# AstroEQ.net
KiCad netlist of a schematic drawn in EAGLE
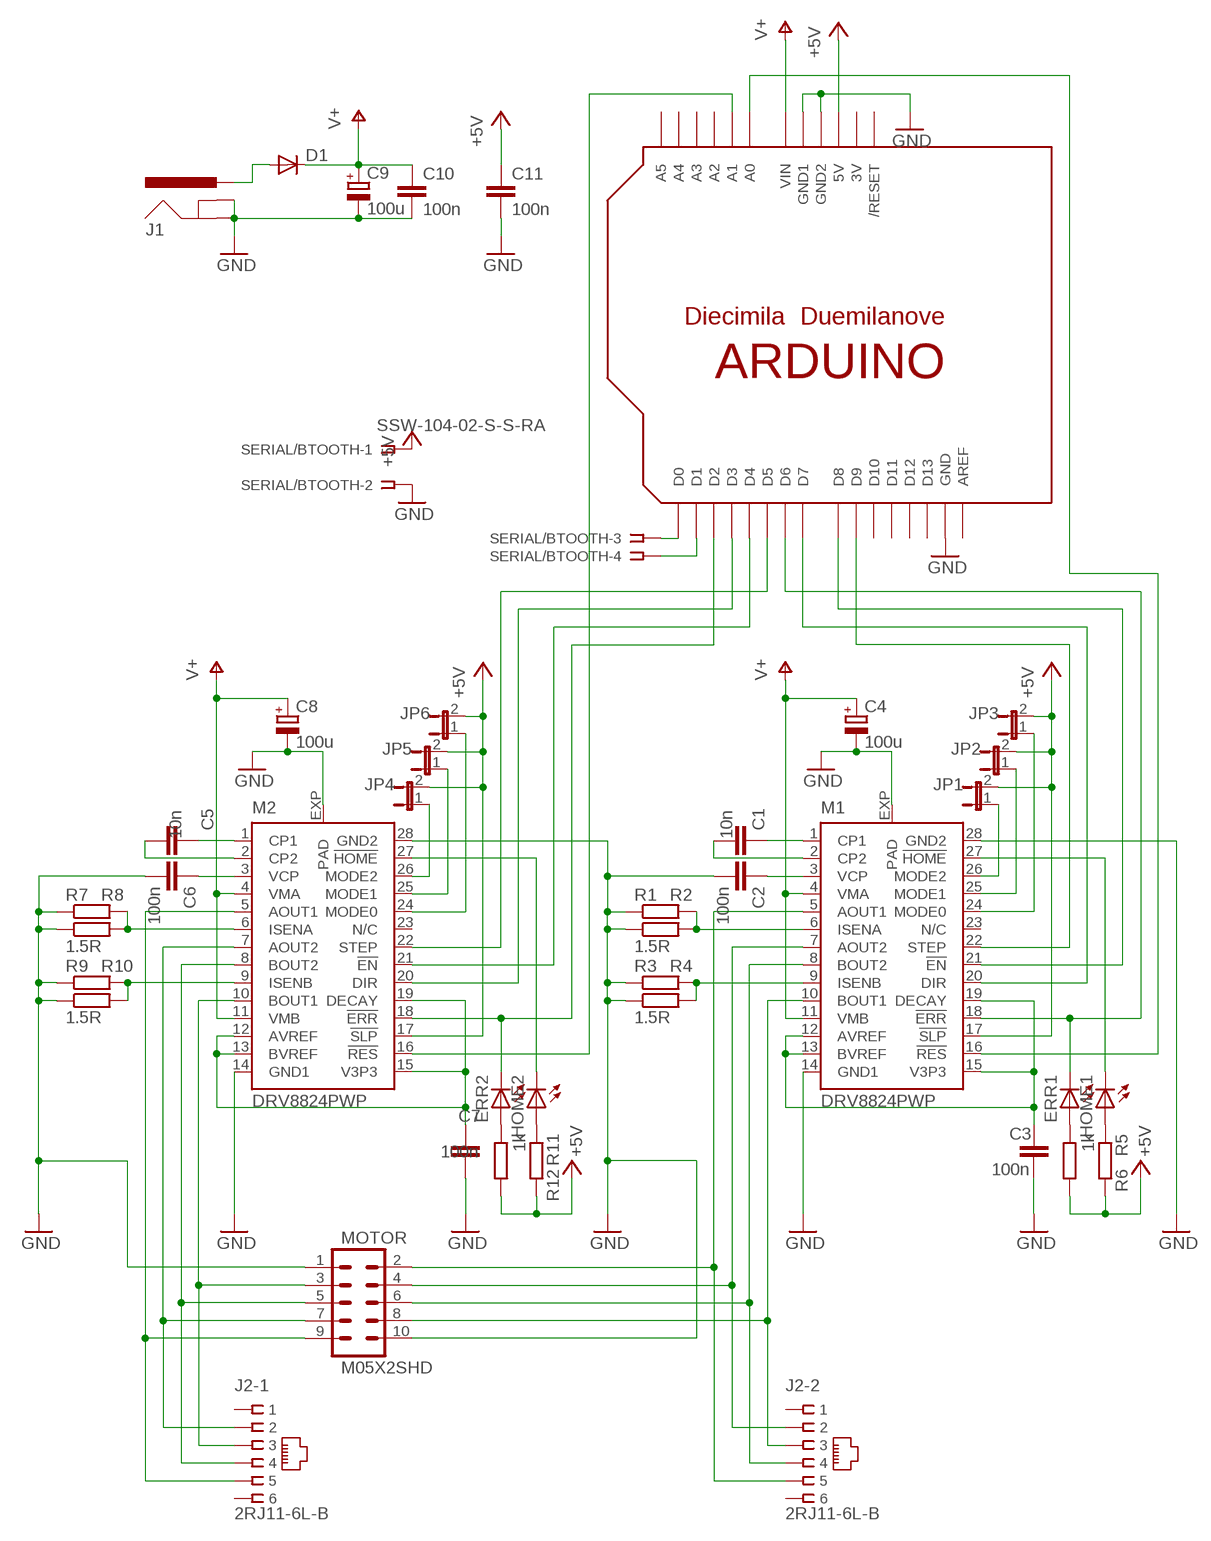
[diagram p0: schematic, sheet 1]

(export (version "E")
  (design (tool "Eeschema 10.0.6"))
  (components
    (comp (ref "C1")
      (value "10n")
      (footprint "eagle-import:C0603K")
      (libsource (lib "eagle-import") (part "C-EUC0603K"))
    )
    (comp (ref "C2")
      (value "100n")
      (footprint "eagle-import:C0603K")
      (libsource (lib "eagle-import") (part "C-EUC0603K"))
    )
    (comp (ref "C3")
      (value "100n")
      (footprint "eagle-import:C0603K")
      (libsource (lib "eagle-import") (part "C-EUC0603K"))
    )
    (comp (ref "C4")
      (value "100u")
      (footprint "eagle-import:C_6032-28R")
      (libsource (lib "eagle-import") (part "CPOL-EUC/6032-28R"))
    )
    (comp (ref "C5")
      (value "10n")
      (footprint "eagle-import:C0603K")
      (libsource (lib "eagle-import") (part "C-EUC0603K"))
    )
    (comp (ref "C6")
      (value "100n")
      (footprint "eagle-import:C0603K")
      (libsource (lib "eagle-import") (part "C-EUC0603K"))
    )
    (comp (ref "C7")
      (value "100n")
      (footprint "eagle-import:C0603K")
      (libsource (lib "eagle-import") (part "C-EUC0603K"))
    )
    (comp (ref "C8")
      (value "100u")
      (footprint "eagle-import:C_6032-28R")
      (libsource (lib "eagle-import") (part "CPOL-EUC/6032-28R"))
    )
    (comp (ref "C9")
      (value "100u")
      (footprint "eagle-import:C_6032-28R")
      (libsource (lib "eagle-import") (part "CPOL-EUC/6032-28R"))
    )
    (comp (ref "C10")
      (value "100n")
      (footprint "eagle-import:C0603K")
      (libsource (lib "eagle-import") (part "C-EUC0603K"))
    )
    (comp (ref "C11")
      (value "100n")
      (footprint "eagle-import:C0603K")
      (libsource (lib "eagle-import") (part "C-EUC0603K"))
    )
    (comp (ref "D1")
      (value "DIODESMA-ALT")
      (footprint "eagle-import:SMA-DIODE_ALT")
      (libsource (lib "eagle-import") (part "DIODESMA-ALT"))
    )
    (comp (ref "ERR1")
      (value "LEDCHIP-LED0603")
      (footprint "eagle-import:CHIP-LED0603")
      (libsource (lib "eagle-import") (part "LEDCHIP-LED0603"))
    )
    (comp (ref "ERR2")
      (value "LEDCHIP-LED0603")
      (footprint "eagle-import:CHIP-LED0603")
      (libsource (lib "eagle-import") (part "LEDCHIP-LED0603"))
    )
    (comp (ref "HOME1")
      (value "LEDCHIP-LED0603")
      (footprint "eagle-import:CHIP-LED0603")
      (libsource (lib "eagle-import") (part "LEDCHIP-LED0603"))
    )
    (comp (ref "HOME2")
      (value "LEDCHIP-LED0603")
      (footprint "eagle-import:CHIP-LED0603")
      (libsource (lib "eagle-import") (part "LEDCHIP-LED0603"))
    )
    (comp (ref "J1")
      (value "POWER_JACKPTH")
      (footprint "eagle-import:POWER_JACK_PTH")
      (libsource (lib "eagle-import") (part "POWER_JACKPTH"))
    )
    (comp (ref "J2")
      (value "2RJ11-6L-B")
      (footprint "eagle-import:2RJ11")
      (fields (field (name "MF") "TYCO ELECTRONICS"))
      (libsource (lib "eagle-import") (part "2RJ11-6L-B"))
    )
    (comp (ref "JP1")
      (value "JUMPER-2SMD-NO")
      (footprint "eagle-import:SJ_2S-NO")
      (libsource (lib "eagle-import") (part "JUMPER-2SMD-NO"))
    )
    (comp (ref "JP2")
      (value "JUMPER-2SMD-NO")
      (footprint "eagle-import:SJ_2S-NO")
      (libsource (lib "eagle-import") (part "JUMPER-2SMD-NO"))
    )
    (comp (ref "JP3")
      (value "JUMPER-2SMD-NO")
      (footprint "eagle-import:SJ_2S-NO")
      (libsource (lib "eagle-import") (part "JUMPER-2SMD-NO"))
    )
    (comp (ref "JP4")
      (value "JUMPER-2SMD-NO")
      (footprint "eagle-import:SJ_2S-NO")
      (libsource (lib "eagle-import") (part "JUMPER-2SMD-NO"))
    )
    (comp (ref "JP5")
      (value "JUMPER-2SMD-NO")
      (footprint "eagle-import:SJ_2S-NO")
      (libsource (lib "eagle-import") (part "JUMPER-2SMD-NO"))
    )
    (comp (ref "JP6")
      (value "JUMPER-2SMD-NO")
      (footprint "eagle-import:SJ_2S-NO")
      (libsource (lib "eagle-import") (part "JUMPER-2SMD-NO"))
    )
    (comp (ref "M1")
      (value "DRV8824PWP")
      (footprint "eagle-import:HTSSOP28PWP")
      (libsource (lib "eagle-import") (part "DRV8824PWP"))
    )
    (comp (ref "M2")
      (value "DRV8824PWP")
      (footprint "eagle-import:HTSSOP28PWP")
      (libsource (lib "eagle-import") (part "DRV8824PWP"))
    )
    (comp (ref "MOTOR")
      (value "M05X2SHD")
      (footprint "eagle-import:2X5-SHROUDED")
      (libsource (lib "eagle-import") (part "M05X2SHD"))
    )
    (comp (ref "R1")
      (value "1.5R")
      (footprint "eagle-import:R2512")
      (libsource (lib "eagle-import") (part "R-EU_R2512"))
    )
    (comp (ref "R2")
      (value "1.5R")
      (footprint "eagle-import:R2512")
      (libsource (lib "eagle-import") (part "R-EU_R2512"))
    )
    (comp (ref "R3")
      (value "1.5R")
      (footprint "eagle-import:R2512")
      (libsource (lib "eagle-import") (part "R-EU_R2512"))
    )
    (comp (ref "R4")
      (value "1.5R")
      (footprint "eagle-import:R2512")
      (libsource (lib "eagle-import") (part "R-EU_R2512"))
    )
    (comp (ref "R5")
      (value "1k")
      (footprint "eagle-import:R0603")
      (libsource (lib "eagle-import") (part "R-EU_R0603"))
    )
    (comp (ref "R6")
      (value "1k")
      (footprint "eagle-import:R0603")
      (libsource (lib "eagle-import") (part "R-EU_R0603"))
    )
    (comp (ref "R7")
      (value "1.5R")
      (footprint "eagle-import:R2512")
      (libsource (lib "eagle-import") (part "R-EU_R2512"))
    )
    (comp (ref "R8")
      (value "1.5R")
      (footprint "eagle-import:R2512")
      (libsource (lib "eagle-import") (part "R-EU_R2512"))
    )
    (comp (ref "R9")
      (value "1.5R")
      (footprint "eagle-import:R2512")
      (libsource (lib "eagle-import") (part "R-EU_R2512"))
    )
    (comp (ref "R10")
      (value "1.5R")
      (footprint "eagle-import:R2512")
      (libsource (lib "eagle-import") (part "R-EU_R2512"))
    )
    (comp (ref "R11")
      (value "1k")
      (footprint "eagle-import:R0603")
      (libsource (lib "eagle-import") (part "R-EU_R0603"))
    )
    (comp (ref "R12")
      (value "1k")
      (footprint "eagle-import:R0603")
      (libsource (lib "eagle-import") (part "R-EU_R0603"))
    )
    (comp (ref "SERIAL/BTOOTH")
      (value "SSW-104-02-S-S-RA")
      (footprint "eagle-import:SSW-104-02-S-S-RA")
      (libsource (lib "eagle-import") (part "SSW-104-02-S-S-RA"))
    )
    (comp (ref "U$1")
      (value "ARDUINOUNO")
      (footprint "eagle-import:ARDUINO")
      (libsource (lib "eagle-import") (part "ARDUINOUNO"))
    )
  )
  (nets
    (net (code "1") (name "+5V") (class "Default")
      (node (ref "C11") (pin "1") (pinfunction "1_1") (pintype "passive"))
      (node (ref "JP1") (pin "2") (pinfunction "2_2") (pintype "passive"))
      (node (ref "JP2") (pin "2") (pinfunction "2_2") (pintype "passive"))
      (node (ref "JP3") (pin "2") (pinfunction "2_2") (pintype "passive"))
      (node (ref "JP4") (pin "2") (pinfunction "2_2") (pintype "passive"))
      (node (ref "JP5") (pin "2") (pinfunction "2_2") (pintype "passive"))
      (node (ref "JP6") (pin "2") (pinfunction "2_2") (pintype "passive"))
      (node (ref "M1") (pin "17") (pinfunction "~{SLP}_17") (pintype "input"))
      (node (ref "M2") (pin "17") (pinfunction "~{SLP}_17") (pintype "input"))
      (node (ref "R11") (pin "2") (pinfunction "2_2") (pintype "passive"))
      (node (ref "R12") (pin "2") (pinfunction "2_2") (pintype "passive"))
      (node (ref "R5") (pin "2") (pinfunction "2_2") (pintype "passive"))
      (node (ref "R6") (pin "2") (pinfunction "2_2") (pintype "passive"))
      (node (ref "SERIAL/BTOOTH") (pin "1") (pinfunction "1_1") (pintype "passive"))
      (node (ref "U$1") (pin "5V") (pinfunction "5V_5V") (pintype "power_in"))
    )
    (net (code "2") (name "/3V") (class "Default")
      (node (ref "U$1") (pin "3V") (pinfunction "3V_3V") (pintype "power_in"))
    )
    (net (code "3") (name "GND") (class "Default")
      (node (ref "C10") (pin "2") (pinfunction "2_2") (pintype "passive"))
      (node (ref "C11") (pin "2") (pinfunction "2_2") (pintype "passive"))
      (node (ref "C2") (pin "2") (pinfunction "2_2") (pintype "passive"))
      (node (ref "C3") (pin "2") (pinfunction "2_2") (pintype "passive"))
      (node (ref "C4") (pin "-") (pinfunction "-_-") (pintype "passive"))
      (node (ref "C6") (pin "2") (pinfunction "2_2") (pintype "passive"))
      (node (ref "C7") (pin "2") (pinfunction "2_2") (pintype "passive"))
      (node (ref "C8") (pin "-") (pinfunction "-_-") (pintype "passive"))
      (node (ref "C9") (pin "-") (pinfunction "-_-") (pintype "passive"))
      (node (ref "J1") (pin "GND") (pinfunction "GND_GND") (pintype "bidirectional"))
      (node (ref "J1") (pin "GNDBREAK") (pinfunction "GNDBREAK_GNDBREAK") (pintype "bidirectional"))
      (node (ref "M1") (pin "14") (pinfunction "GND1_14") (pintype "power_in"))
      (node (ref "M1") (pin "28") (pinfunction "GND2_28") (pintype "power_in"))
      (node (ref "M1") (pin "EXP") (pinfunction "PAD_EXP") (pintype "power_in"))
      (node (ref "M2") (pin "14") (pinfunction "GND1_14") (pintype "power_in"))
      (node (ref "M2") (pin "28") (pinfunction "GND2_28") (pintype "power_in"))
      (node (ref "M2") (pin "EXP") (pinfunction "PAD_EXP") (pintype "power_in"))
      (node (ref "MOTOR") (pin "1") (pinfunction "1_1") (pintype "passive"))
      (node (ref "MOTOR") (pin "10") (pinfunction "10_10") (pintype "passive"))
      (node (ref "R1") (pin "1") (pinfunction "1_1") (pintype "passive"))
      (node (ref "R10") (pin "1") (pinfunction "1_1") (pintype "passive"))
      (node (ref "R2") (pin "1") (pinfunction "1_1") (pintype "passive"))
      (node (ref "R3") (pin "1") (pinfunction "1_1") (pintype "passive"))
      (node (ref "R4") (pin "1") (pinfunction "1_1") (pintype "passive"))
      (node (ref "R7") (pin "1") (pinfunction "1_1") (pintype "passive"))
      (node (ref "R8") (pin "1") (pinfunction "1_1") (pintype "passive"))
      (node (ref "R9") (pin "1") (pinfunction "1_1") (pintype "passive"))
      (node (ref "SERIAL/BTOOTH") (pin "2") (pinfunction "1_2") (pintype "passive"))
      (node (ref "U$1") (pin "GND") (pinfunction "GND_GND") (pintype "power_in"))
      (node (ref "U$1") (pin "GND1") (pinfunction "GND1_GND1") (pintype "power_in"))
      (node (ref "U$1") (pin "GND2") (pinfunction "GND2_GND2") (pintype "power_in"))
    )
    (net (code "4") (name "Net-(D1-PadA)") (class "Default")
      (node (ref "D1") (pin "A") (pinfunction "A_A") (pintype "passive"))
      (node (ref "J1") (pin "PWR") (pinfunction "PWR_PWR") (pintype "bidirectional"))
    )
    (net (code "5") (name "Net-(ERR1-PadA)") (class "Default")
      (node (ref "ERR1") (pin "A") (pinfunction "A_A") (pintype "passive"))
      (node (ref "R6") (pin "1") (pinfunction "1_1") (pintype "passive"))
    )
    (net (code "6") (name "Net-(ERR2-PadA)") (class "Default")
      (node (ref "ERR2") (pin "A") (pinfunction "A_A") (pintype "passive"))
      (node (ref "R12") (pin "1") (pinfunction "1_1") (pintype "passive"))
    )
    (net (code "7") (name "Net-(HOME1-PadA)") (class "Default")
      (node (ref "HOME1") (pin "A") (pinfunction "A_A") (pintype "passive"))
      (node (ref "R5") (pin "1") (pinfunction "1_1") (pintype "passive"))
    )
    (net (code "8") (name "Net-(HOME2-PadA)") (class "Default")
      (node (ref "HOME2") (pin "A") (pinfunction "A_A") (pintype "passive"))
      (node (ref "R11") (pin "1") (pinfunction "1_1") (pintype "passive"))
    )
    (net (code "9") (name "Net-(J2A-2)") (class "Default")
      (node (ref "J2") (pin "1-2") (pinfunction "2_1-2") (pintype "passive"))
      (node (ref "M2") (pin "7") (pinfunction "AOUT2_7") (pintype "output"))
      (node (ref "MOTOR") (pin "7") (pinfunction "7_7") (pintype "passive"))
    )
    (net (code "10") (name "Net-(J2A-3)") (class "Default")
      (node (ref "J2") (pin "1-3") (pinfunction "3_1-3") (pintype "passive"))
      (node (ref "M2") (pin "10") (pinfunction "BOUT1_10") (pintype "output"))
      (node (ref "MOTOR") (pin "3") (pinfunction "3_3") (pintype "passive"))
    )
    (net (code "11") (name "Net-(J2A-4)") (class "Default")
      (node (ref "J2") (pin "1-4") (pinfunction "4_1-4") (pintype "passive"))
      (node (ref "M2") (pin "8") (pinfunction "BOUT2_8") (pintype "output"))
      (node (ref "MOTOR") (pin "5") (pinfunction "5_5") (pintype "passive"))
    )
    (net (code "12") (name "Net-(J2A-5)") (class "Default")
      (node (ref "J2") (pin "1-5") (pinfunction "5_1-5") (pintype "passive"))
      (node (ref "M2") (pin "5") (pinfunction "AOUT1_5") (pintype "output"))
      (node (ref "MOTOR") (pin "9") (pinfunction "9_9") (pintype "passive"))
    )
    (net (code "13") (name "Net-(J2B-2)") (class "Default")
      (node (ref "J2") (pin "2-2") (pinfunction "2_2-2") (pintype "passive"))
      (node (ref "M1") (pin "7") (pinfunction "AOUT2_7") (pintype "output"))
      (node (ref "MOTOR") (pin "4") (pinfunction "4_4") (pintype "passive"))
    )
    (net (code "14") (name "Net-(J2B-3)") (class "Default")
      (node (ref "J2") (pin "2-3") (pinfunction "3_2-3") (pintype "passive"))
      (node (ref "M1") (pin "10") (pinfunction "BOUT1_10") (pintype "output"))
      (node (ref "MOTOR") (pin "8") (pinfunction "8_8") (pintype "passive"))
    )
    (net (code "15") (name "Net-(J2B-4)") (class "Default")
      (node (ref "J2") (pin "2-4") (pinfunction "4_2-4") (pintype "passive"))
      (node (ref "M1") (pin "8") (pinfunction "BOUT2_8") (pintype "output"))
      (node (ref "MOTOR") (pin "6") (pinfunction "6_6") (pintype "passive"))
    )
    (net (code "16") (name "Net-(J2B-5)") (class "Default")
      (node (ref "J2") (pin "2-5") (pinfunction "5_2-5") (pintype "passive"))
      (node (ref "M1") (pin "5") (pinfunction "AOUT1_5") (pintype "output"))
      (node (ref "MOTOR") (pin "2") (pinfunction "2_2") (pintype "passive"))
    )
    (net (code "17") (name "Net-(M1-AVREF)") (class "Default")
      (node (ref "C3") (pin "1") (pinfunction "1_1") (pintype "passive"))
      (node (ref "M1") (pin "12") (pinfunction "AVREF_12") (pintype "input"))
      (node (ref "M1") (pin "13") (pinfunction "BVREF_13") (pintype "input"))
      (node (ref "M1") (pin "15") (pinfunction "V3P3_15") (pintype "output"))
      (node (ref "M1") (pin "19") (pinfunction "DECAY_19") (pintype "input"))
    )
    (net (code "18") (name "Net-(M1-CP1)") (class "Default")
      (node (ref "C1") (pin "1") (pinfunction "1_1") (pintype "passive"))
      (node (ref "M1") (pin "1") (pinfunction "CP1_1") (pintype "passive"))
    )
    (net (code "19") (name "Net-(M1-CP2)") (class "Default")
      (node (ref "C1") (pin "2") (pinfunction "2_2") (pintype "passive"))
      (node (ref "M1") (pin "2") (pinfunction "CP2_2") (pintype "passive"))
    )
    (net (code "20") (name "Net-(M1-DIR)") (class "Default")
      (node (ref "M1") (pin "20") (pinfunction "DIR_20") (pintype "input"))
      (node (ref "U$1") (pin "D7") (pinfunction "D7_D7") (pintype "bidirectional"))
    )
    (net (code "21") (name "Net-(M1-ISENA)") (class "Default")
      (node (ref "M1") (pin "6") (pinfunction "ISENA_6") (pintype "bidirectional"))
      (node (ref "R1") (pin "2") (pinfunction "2_2") (pintype "passive"))
      (node (ref "R2") (pin "2") (pinfunction "2_2") (pintype "passive"))
    )
    (net (code "22") (name "Net-(M1-ISENB)") (class "Default")
      (node (ref "M1") (pin "9") (pinfunction "ISENB_9") (pintype "bidirectional"))
      (node (ref "R3") (pin "2") (pinfunction "2_2") (pintype "passive"))
      (node (ref "R4") (pin "2") (pinfunction "2_2") (pintype "passive"))
    )
    (net (code "23") (name "Net-(M1-MODE0)") (class "Default")
      (node (ref "JP3") (pin "1") (pinfunction "1_1") (pintype "passive"))
      (node (ref "M1") (pin "24") (pinfunction "MODE0_24") (pintype "input"))
    )
    (net (code "24") (name "Net-(M1-MODE1)") (class "Default")
      (node (ref "JP2") (pin "1") (pinfunction "1_1") (pintype "passive"))
      (node (ref "M1") (pin "25") (pinfunction "MODE1_25") (pintype "input"))
    )
    (net (code "25") (name "Net-(M1-MODE2)") (class "Default")
      (node (ref "JP1") (pin "1") (pinfunction "1_1") (pintype "passive"))
      (node (ref "M1") (pin "26") (pinfunction "MODE2_26") (pintype "input"))
    )
    (net (code "26") (name "Net-(M1-STEP)") (class "Default")
      (node (ref "M1") (pin "22") (pinfunction "STEP_22") (pintype "input"))
      (node (ref "U$1") (pin "D9") (pinfunction "D9_D9") (pintype "bidirectional"))
    )
    (net (code "27") (name "Net-(M1-VCP)") (class "Default")
      (node (ref "C2") (pin "1") (pinfunction "1_1") (pintype "passive"))
      (node (ref "M1") (pin "3") (pinfunction "VCP_3") (pintype "power_in"))
    )
    (net (code "28") (name "Net-(M1-~{EN})") (class "Default")
      (node (ref "M1") (pin "21") (pinfunction "~{EN}_21") (pintype "input"))
      (node (ref "U$1") (pin "D8") (pinfunction "D8_D8") (pintype "bidirectional"))
    )
    (net (code "29") (name "Net-(M1-~{ERR})") (class "Default")
      (node (ref "ERR1") (pin "C") (pinfunction "C_C") (pintype "passive"))
      (node (ref "M1") (pin "18") (pinfunction "~{ERR}_18") (pintype "output"))
      (node (ref "U$1") (pin "D6") (pinfunction "D6_D6") (pintype "bidirectional"))
    )
    (net (code "30") (name "Net-(M1-~{HOME})") (class "Default")
      (node (ref "HOME1") (pin "C") (pinfunction "C_C") (pintype "passive"))
      (node (ref "M1") (pin "27") (pinfunction "~{HOME}_27") (pintype "output"))
    )
    (net (code "31") (name "Net-(M1-~{RES})") (class "Default")
      (node (ref "M1") (pin "16") (pinfunction "~{RES}_16") (pintype "input"))
      (node (ref "U$1") (pin "A0") (pinfunction "A0_A0") (pintype "bidirectional"))
    )
    (net (code "32") (name "Net-(M2-AVREF)") (class "Default")
      (node (ref "C7") (pin "1") (pinfunction "1_1") (pintype "passive"))
      (node (ref "M2") (pin "12") (pinfunction "AVREF_12") (pintype "input"))
      (node (ref "M2") (pin "13") (pinfunction "BVREF_13") (pintype "input"))
      (node (ref "M2") (pin "15") (pinfunction "V3P3_15") (pintype "output"))
      (node (ref "M2") (pin "19") (pinfunction "DECAY_19") (pintype "input"))
    )
    (net (code "33") (name "Net-(M2-CP1)") (class "Default")
      (node (ref "C5") (pin "1") (pinfunction "1_1") (pintype "passive"))
      (node (ref "M2") (pin "1") (pinfunction "CP1_1") (pintype "passive"))
    )
    (net (code "34") (name "Net-(M2-CP2)") (class "Default")
      (node (ref "C5") (pin "2") (pinfunction "2_2") (pintype "passive"))
      (node (ref "M2") (pin "2") (pinfunction "CP2_2") (pintype "passive"))
    )
    (net (code "35") (name "Net-(M2-DIR)") (class "Default")
      (node (ref "M2") (pin "20") (pinfunction "DIR_20") (pintype "input"))
      (node (ref "U$1") (pin "D3") (pinfunction "D3_D3") (pintype "bidirectional"))
    )
    (net (code "36") (name "Net-(M2-ISENA)") (class "Default")
      (node (ref "M2") (pin "6") (pinfunction "ISENA_6") (pintype "bidirectional"))
      (node (ref "R7") (pin "2") (pinfunction "2_2") (pintype "passive"))
      (node (ref "R8") (pin "2") (pinfunction "2_2") (pintype "passive"))
    )
    (net (code "37") (name "Net-(M2-ISENB)") (class "Default")
      (node (ref "M2") (pin "9") (pinfunction "ISENB_9") (pintype "bidirectional"))
      (node (ref "R10") (pin "2") (pinfunction "2_2") (pintype "passive"))
      (node (ref "R9") (pin "2") (pinfunction "2_2") (pintype "passive"))
    )
    (net (code "38") (name "Net-(M2-MODE0)") (class "Default")
      (node (ref "JP6") (pin "1") (pinfunction "1_1") (pintype "passive"))
      (node (ref "M2") (pin "24") (pinfunction "MODE0_24") (pintype "input"))
    )
    (net (code "39") (name "Net-(M2-MODE1)") (class "Default")
      (node (ref "JP5") (pin "1") (pinfunction "1_1") (pintype "passive"))
      (node (ref "M2") (pin "25") (pinfunction "MODE1_25") (pintype "input"))
    )
    (net (code "40") (name "Net-(M2-MODE2)") (class "Default")
      (node (ref "JP4") (pin "1") (pinfunction "1_1") (pintype "passive"))
      (node (ref "M2") (pin "26") (pinfunction "MODE2_26") (pintype "input"))
    )
    (net (code "41") (name "Net-(M2-STEP)") (class "Default")
      (node (ref "M2") (pin "22") (pinfunction "STEP_22") (pintype "input"))
      (node (ref "U$1") (pin "D5") (pinfunction "D5_D5") (pintype "bidirectional"))
    )
    (net (code "42") (name "Net-(M2-VCP)") (class "Default")
      (node (ref "C6") (pin "1") (pinfunction "1_1") (pintype "passive"))
      (node (ref "M2") (pin "3") (pinfunction "VCP_3") (pintype "power_in"))
    )
    (net (code "43") (name "Net-(M2-~{EN})") (class "Default")
      (node (ref "M2") (pin "21") (pinfunction "~{EN}_21") (pintype "input"))
      (node (ref "U$1") (pin "D4") (pinfunction "D4_D4") (pintype "bidirectional"))
    )
    (net (code "44") (name "Net-(M2-~{ERR})") (class "Default")
      (node (ref "ERR2") (pin "C") (pinfunction "C_C") (pintype "passive"))
      (node (ref "M2") (pin "18") (pinfunction "~{ERR}_18") (pintype "output"))
      (node (ref "U$1") (pin "D2") (pinfunction "D2_D2") (pintype "bidirectional"))
    )
    (net (code "45") (name "Net-(M2-~{HOME})") (class "Default")
      (node (ref "HOME2") (pin "C") (pinfunction "C_C") (pintype "passive"))
      (node (ref "M2") (pin "27") (pinfunction "~{HOME}_27") (pintype "output"))
    )
    (net (code "46") (name "Net-(M2-~{RES})") (class "Default")
      (node (ref "M2") (pin "16") (pinfunction "~{RES}_16") (pintype "input"))
      (node (ref "U$1") (pin "A1") (pinfunction "A1_A1") (pintype "bidirectional"))
    )
    (net (code "47") (name "Net-(SERIAL/BTOOTHC-1)") (class "Default")
      (node (ref "SERIAL/BTOOTH") (pin "3") (pinfunction "1_3") (pintype "passive"))
      (node (ref "U$1") (pin "D0") (pinfunction "D0_D0") (pintype "bidirectional"))
    )
    (net (code "48") (name "Net-(SERIAL/BTOOTHD-1)") (class "Default")
      (node (ref "SERIAL/BTOOTH") (pin "4") (pinfunction "1_4") (pintype "passive"))
      (node (ref "U$1") (pin "D1") (pinfunction "D1_D1") (pintype "bidirectional"))
    )
    (net (code "49") (name "V+") (class "Default")
      (node (ref "C10") (pin "1") (pinfunction "1_1") (pintype "passive"))
      (node (ref "C4") (pin "+") (pinfunction "+_+") (pintype "passive"))
      (node (ref "C8") (pin "+") (pinfunction "+_+") (pintype "passive"))
      (node (ref "C9") (pin "+") (pinfunction "+_+") (pintype "passive"))
      (node (ref "D1") (pin "C") (pinfunction "C_C") (pintype "passive"))
      (node (ref "M1") (pin "11") (pinfunction "VMB_11") (pintype "power_in"))
      (node (ref "M1") (pin "4") (pinfunction "VMA_4") (pintype "power_in"))
      (node (ref "M2") (pin "11") (pinfunction "VMB_11") (pintype "power_in"))
      (node (ref "M2") (pin "4") (pinfunction "VMA_4") (pintype "power_in"))
      (node (ref "U$1") (pin "VIN") (pinfunction "VIN_VIN") (pintype "power_in"))
    )
    (net (code "50") (name "unconnected-(J2A-1-Pad1-1)") (class "Default")
      (node (ref "J2") (pin "1-1") (pinfunction "1_1-1") (pintype "passive"))
    )
    (net (code "51") (name "unconnected-(J2A-6-Pad1-6)") (class "Default")
      (node (ref "J2") (pin "1-6") (pinfunction "6_1-6") (pintype "passive"))
    )
    (net (code "52") (name "unconnected-(J2B-1-Pad2-1)") (class "Default")
      (node (ref "J2") (pin "2-1") (pinfunction "1_2-1") (pintype "passive"))
    )
    (net (code "53") (name "unconnected-(J2B-6-Pad2-6)") (class "Default")
      (node (ref "J2") (pin "2-6") (pinfunction "6_2-6") (pintype "passive"))
    )
    (net (code "54") (name "unconnected-(M1-N{slash}C-Pad23)") (class "Default")
      (node (ref "M1") (pin "23") (pinfunction "N/C_23") (pintype "no_connect"))
    )
    (net (code "55") (name "unconnected-(M2-N{slash}C-Pad23)") (class "Default")
      (node (ref "M2") (pin "23") (pinfunction "N/C_23") (pintype "no_connect"))
    )
    (net (code "56") (name "unconnected-(U$1-PadA2)") (class "Default")
      (node (ref "U$1") (pin "A2") (pinfunction "A2_A2") (pintype "bidirectional"))
    )
    (net (code "57") (name "unconnected-(U$1-PadA3)") (class "Default")
      (node (ref "U$1") (pin "A3") (pinfunction "A3_A3") (pintype "bidirectional"))
    )
    (net (code "58") (name "unconnected-(U$1-PadA4)") (class "Default")
      (node (ref "U$1") (pin "A4") (pinfunction "A4_A4") (pintype "bidirectional"))
    )
    (net (code "59") (name "unconnected-(U$1-PadA5)") (class "Default")
      (node (ref "U$1") (pin "A5") (pinfunction "A5_A5") (pintype "bidirectional"))
    )
    (net (code "60") (name "unconnected-(U$1-PadAREF)") (class "Default")
      (node (ref "U$1") (pin "AREF") (pinfunction "AREF_AREF") (pintype "bidirectional"))
    )
    (net (code "61") (name "unconnected-(U$1-PadD10)") (class "Default")
      (node (ref "U$1") (pin "D10") (pinfunction "D10_D10") (pintype "bidirectional"))
    )
    (net (code "62") (name "unconnected-(U$1-PadD11)") (class "Default")
      (node (ref "U$1") (pin "D11") (pinfunction "D11_D11") (pintype "bidirectional"))
    )
    (net (code "63") (name "unconnected-(U$1-PadD12)") (class "Default")
      (node (ref "U$1") (pin "D12") (pinfunction "D12_D12") (pintype "bidirectional"))
    )
    (net (code "64") (name "unconnected-(U$1-PadD13)") (class "Default")
      (node (ref "U$1") (pin "D13") (pinfunction "D13_D13") (pintype "bidirectional"))
    )
    (net (code "65") (name "unconnected-(U$1-{slash}RESET-PadRESET)") (class "Default")
      (node (ref "U$1") (pin "RESET") (pinfunction "/RESET_RESET") (pintype "bidirectional"))
    )
  )
)
